# badge.net
KiCad netlist of a schematic drawn in EAGLE
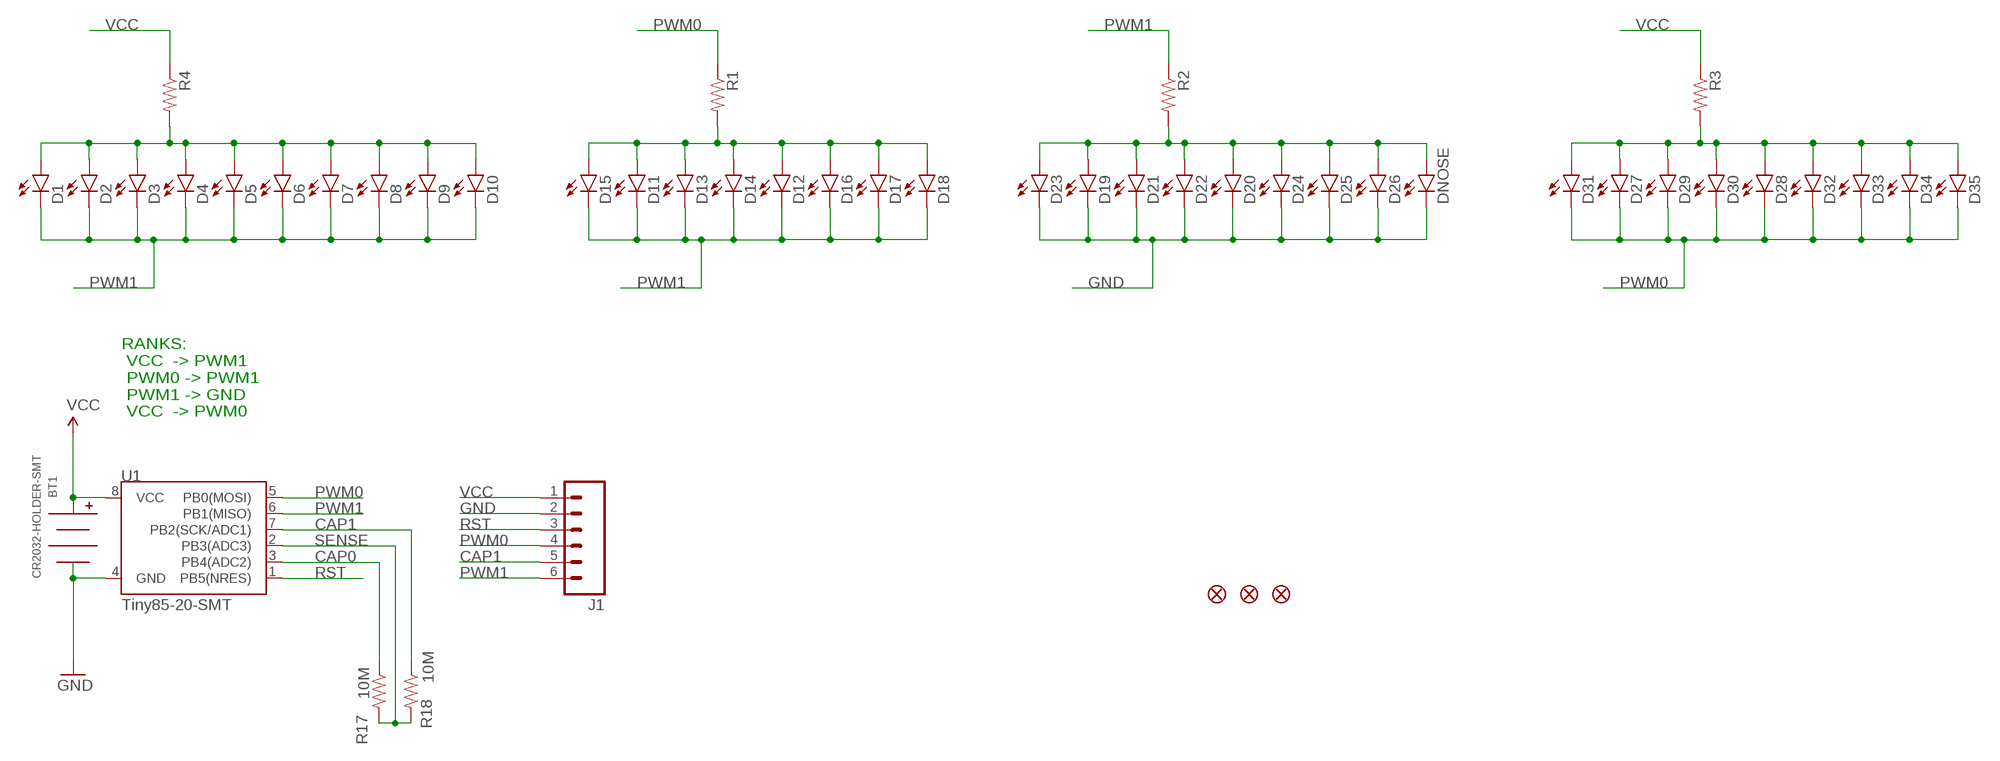
[diagram p0: schematic, sheet 1]

(export (version "E")
  (design (tool "Eeschema 10.0.6"))
  (components
    (comp (ref "BT1")
      (value "CR2032-HOLDER-SMT")
      (footprint "eagle-import:S8211-46R")
      (libsource (lib "eagle-import") (part "CR2032-HOLDER-SMT"))
    )
    (comp (ref "D1")
      (value "LED0603")
      (footprint "eagle-import:LED-0603")
      (libsource (lib "eagle-import") (part "LED0603"))
    )
    (comp (ref "D2")
      (value "LED0603")
      (footprint "eagle-import:LED-0603")
      (libsource (lib "eagle-import") (part "LED0603"))
    )
    (comp (ref "D3")
      (value "LED0603")
      (footprint "eagle-import:LED-0603")
      (libsource (lib "eagle-import") (part "LED0603"))
    )
    (comp (ref "D4")
      (value "LED0603")
      (footprint "eagle-import:LED-0603")
      (libsource (lib "eagle-import") (part "LED0603"))
    )
    (comp (ref "D5")
      (value "LED0603")
      (footprint "eagle-import:LED-0603")
      (libsource (lib "eagle-import") (part "LED0603"))
    )
    (comp (ref "D6")
      (value "LED0603")
      (footprint "eagle-import:LED-0603")
      (libsource (lib "eagle-import") (part "LED0603"))
    )
    (comp (ref "D7")
      (value "LED0603")
      (footprint "eagle-import:LED-0603")
      (libsource (lib "eagle-import") (part "LED0603"))
    )
    (comp (ref "D8")
      (value "LED0603")
      (footprint "eagle-import:LED-0603")
      (libsource (lib "eagle-import") (part "LED0603"))
    )
    (comp (ref "D9")
      (value "LED0603")
      (footprint "eagle-import:LED-0603")
      (libsource (lib "eagle-import") (part "LED0603"))
    )
    (comp (ref "D10")
      (value "LED0603")
      (footprint "eagle-import:LED-0603")
      (libsource (lib "eagle-import") (part "LED0603"))
    )
    (comp (ref "D11")
      (value "LED0603")
      (footprint "eagle-import:LED-0603")
      (libsource (lib "eagle-import") (part "LED0603"))
    )
    (comp (ref "D12")
      (value "LED0603")
      (footprint "eagle-import:LED-0603")
      (libsource (lib "eagle-import") (part "LED0603"))
    )
    (comp (ref "D13")
      (value "LED0603")
      (footprint "eagle-import:LED-0603")
      (libsource (lib "eagle-import") (part "LED0603"))
    )
    (comp (ref "D14")
      (value "LED0603")
      (footprint "eagle-import:LED-0603")
      (libsource (lib "eagle-import") (part "LED0603"))
    )
    (comp (ref "D15")
      (value "LED0603")
      (footprint "eagle-import:LED-0603")
      (libsource (lib "eagle-import") (part "LED0603"))
    )
    (comp (ref "D16")
      (value "LED0603")
      (footprint "eagle-import:LED-0603")
      (libsource (lib "eagle-import") (part "LED0603"))
    )
    (comp (ref "D17")
      (value "LED0603")
      (footprint "eagle-import:LED-0603")
      (libsource (lib "eagle-import") (part "LED0603"))
    )
    (comp (ref "D18")
      (value "LED0603")
      (footprint "eagle-import:LED-0603")
      (libsource (lib "eagle-import") (part "LED0603"))
    )
    (comp (ref "D19")
      (value "LED0603")
      (footprint "eagle-import:LED-0603")
      (libsource (lib "eagle-import") (part "LED0603"))
    )
    (comp (ref "D20")
      (value "LED0603")
      (footprint "eagle-import:LED-0603")
      (libsource (lib "eagle-import") (part "LED0603"))
    )
    (comp (ref "D21")
      (value "LED0603")
      (footprint "eagle-import:LED-0603")
      (libsource (lib "eagle-import") (part "LED0603"))
    )
    (comp (ref "D22")
      (value "LED0603")
      (footprint "eagle-import:LED-0603")
      (libsource (lib "eagle-import") (part "LED0603"))
    )
    (comp (ref "D23")
      (value "LED0603")
      (footprint "eagle-import:LED-0603")
      (libsource (lib "eagle-import") (part "LED0603"))
    )
    (comp (ref "D24")
      (value "LED0603")
      (footprint "eagle-import:LED-0603")
      (libsource (lib "eagle-import") (part "LED0603"))
    )
    (comp (ref "D25")
      (value "LED0603")
      (footprint "eagle-import:LED-0603")
      (libsource (lib "eagle-import") (part "LED0603"))
    )
    (comp (ref "D26")
      (value "LED0603")
      (footprint "eagle-import:LED-0603")
      (libsource (lib "eagle-import") (part "LED0603"))
    )
    (comp (ref "D27")
      (value "LED0603")
      (footprint "eagle-import:LED-0603")
      (libsource (lib "eagle-import") (part "LED0603"))
    )
    (comp (ref "D28")
      (value "LED0603")
      (footprint "eagle-import:LED-0603")
      (libsource (lib "eagle-import") (part "LED0603"))
    )
    (comp (ref "D29")
      (value "LED0603")
      (footprint "eagle-import:LED-0603")
      (libsource (lib "eagle-import") (part "LED0603"))
    )
    (comp (ref "D30")
      (value "LED0603")
      (footprint "eagle-import:LED-0603")
      (libsource (lib "eagle-import") (part "LED0603"))
    )
    (comp (ref "D31")
      (value "LED0603")
      (footprint "eagle-import:LED-0603")
      (libsource (lib "eagle-import") (part "LED0603"))
    )
    (comp (ref "D32")
      (value "LED0603")
      (footprint "eagle-import:LED-0603")
      (libsource (lib "eagle-import") (part "LED0603"))
    )
    (comp (ref "D33")
      (value "LED0603")
      (footprint "eagle-import:LED-0603")
      (libsource (lib "eagle-import") (part "LED0603"))
    )
    (comp (ref "D34")
      (value "LED0603")
      (footprint "eagle-import:LED-0603")
      (libsource (lib "eagle-import") (part "LED0603"))
    )
    (comp (ref "D35")
      (value "LED0603")
      (footprint "eagle-import:LED-0603")
      (libsource (lib "eagle-import") (part "LED0603"))
    )
    (comp (ref "DNOSE")
      (value "LED0603")
      (footprint "eagle-import:LED-0603")
      (libsource (lib "eagle-import") (part "LED0603"))
    )
    (comp (ref "FD1")
      (value "FIDUCIAL1X2")
      (footprint "eagle-import:FIDUCIAL-1X2")
      (libsource (lib "eagle-import") (part "FIDUCIAL1X2"))
    )
    (comp (ref "FD2")
      (value "FIDUCIAL1X2")
      (footprint "eagle-import:FIDUCIAL-1X2")
      (libsource (lib "eagle-import") (part "FIDUCIAL1X2"))
    )
    (comp (ref "FD3")
      (value "FIDUCIAL1X2")
      (footprint "eagle-import:FIDUCIAL-1X2")
      (libsource (lib "eagle-import") (part "FIDUCIAL1X2"))
    )
    (comp (ref "J1")
      (value "M06LONGPADS")
      (footprint "eagle-import:1X06_LONGPADS")
      (libsource (lib "eagle-import") (part "M06LONGPADS"))
    )
    (comp (ref "R1")
      (value "RESISTOR1206")
      (footprint "eagle-import:1206")
      (libsource (lib "eagle-import") (part "RESISTOR1206"))
    )
    (comp (ref "R2")
      (value "RESISTOR1206")
      (footprint "eagle-import:1206")
      (libsource (lib "eagle-import") (part "RESISTOR1206"))
    )
    (comp (ref "R3")
      (value "RESISTOR1206")
      (footprint "eagle-import:1206")
      (libsource (lib "eagle-import") (part "RESISTOR1206"))
    )
    (comp (ref "R4")
      (value "RESISTOR1206")
      (footprint "eagle-import:1206")
      (libsource (lib "eagle-import") (part "RESISTOR1206"))
    )
    (comp (ref "R17")
      (value "10M")
      (footprint "eagle-import:0805")
      (libsource (lib "eagle-import") (part "RESISTOR0805-RES"))
    )
    (comp (ref "R18")
      (value "10M")
      (footprint "eagle-import:0805")
      (libsource (lib "eagle-import") (part "RESISTOR0805-RES"))
    )
    (comp (ref "U1")
      (value "Tiny85-20-SMT")
      (footprint "eagle-import:SO08-EIAJ")
      (libsource (lib "eagle-import") (part "ATTINY45TINY85-20-SMT"))
    )
  )
  (nets
    (net (code "1") (name "/CAP0") (class "Default")
      (node (ref "R17") (pin "1") (pinfunction "1_1") (pintype "passive"))
      (node (ref "U1") (pin "3") (pinfunction "PB4(ADC2)_3") (pintype "bidirectional"))
    )
    (net (code "2") (name "/CAP1") (class "Default")
      (node (ref "J1") (pin "5") (pinfunction "5_5") (pintype "passive"))
      (node (ref "R18") (pin "1") (pinfunction "1_1") (pintype "passive"))
      (node (ref "U1") (pin "7") (pinfunction "PB2(SCK/ADC1)_7") (pintype "bidirectional"))
    )
    (net (code "3") (name "/PWM0") (class "Default")
      (node (ref "D27") (pin "C") (pinfunction "C_C") (pintype "passive"))
      (node (ref "D28") (pin "C") (pinfunction "C_C") (pintype "passive"))
      (node (ref "D29") (pin "C") (pinfunction "C_C") (pintype "passive"))
      (node (ref "D30") (pin "C") (pinfunction "C_C") (pintype "passive"))
      (node (ref "D31") (pin "C") (pinfunction "C_C") (pintype "passive"))
      (node (ref "D32") (pin "C") (pinfunction "C_C") (pintype "passive"))
      (node (ref "D33") (pin "C") (pinfunction "C_C") (pintype "passive"))
      (node (ref "D34") (pin "C") (pinfunction "C_C") (pintype "passive"))
      (node (ref "D35") (pin "C") (pinfunction "C_C") (pintype "passive"))
      (node (ref "J1") (pin "4") (pinfunction "4_4") (pintype "passive"))
      (node (ref "R1") (pin "1") (pinfunction "1_1") (pintype "passive"))
      (node (ref "U1") (pin "5") (pinfunction "PB0(MOSI)_5") (pintype "bidirectional"))
    )
    (net (code "4") (name "/PWM1") (class "Default")
      (node (ref "D1") (pin "C") (pinfunction "C_C") (pintype "passive"))
      (node (ref "D10") (pin "C") (pinfunction "C_C") (pintype "passive"))
      (node (ref "D11") (pin "C") (pinfunction "C_C") (pintype "passive"))
      (node (ref "D12") (pin "C") (pinfunction "C_C") (pintype "passive"))
      (node (ref "D13") (pin "C") (pinfunction "C_C") (pintype "passive"))
      (node (ref "D14") (pin "C") (pinfunction "C_C") (pintype "passive"))
      (node (ref "D15") (pin "C") (pinfunction "C_C") (pintype "passive"))
      (node (ref "D16") (pin "C") (pinfunction "C_C") (pintype "passive"))
      (node (ref "D17") (pin "C") (pinfunction "C_C") (pintype "passive"))
      (node (ref "D18") (pin "C") (pinfunction "C_C") (pintype "passive"))
      (node (ref "D2") (pin "C") (pinfunction "C_C") (pintype "passive"))
      (node (ref "D3") (pin "C") (pinfunction "C_C") (pintype "passive"))
      (node (ref "D4") (pin "C") (pinfunction "C_C") (pintype "passive"))
      (node (ref "D5") (pin "C") (pinfunction "C_C") (pintype "passive"))
      (node (ref "D6") (pin "C") (pinfunction "C_C") (pintype "passive"))
      (node (ref "D7") (pin "C") (pinfunction "C_C") (pintype "passive"))
      (node (ref "D8") (pin "C") (pinfunction "C_C") (pintype "passive"))
      (node (ref "D9") (pin "C") (pinfunction "C_C") (pintype "passive"))
      (node (ref "J1") (pin "6") (pinfunction "6_6") (pintype "passive"))
      (node (ref "R2") (pin "1") (pinfunction "1_1") (pintype "passive"))
      (node (ref "U1") (pin "6") (pinfunction "PB1(MISO)_6") (pintype "bidirectional"))
    )
    (net (code "5") (name "/RST") (class "Default")
      (node (ref "J1") (pin "3") (pinfunction "3_3") (pintype "passive"))
      (node (ref "U1") (pin "1") (pinfunction "PB5(NRES)_1") (pintype "bidirectional"))
    )
    (net (code "6") (name "/SENSE") (class "Default")
      (node (ref "R17") (pin "2") (pinfunction "2_2") (pintype "passive"))
      (node (ref "R18") (pin "2") (pinfunction "2_2") (pintype "passive"))
      (node (ref "U1") (pin "2") (pinfunction "PB3(ADC3)_2") (pintype "bidirectional"))
    )
    (net (code "7") (name "GND") (class "Default")
      (node (ref "BT1") (pin "NEG") (pinfunction "NEG_NEG") (pintype "bidirectional"))
      (node (ref "D19") (pin "C") (pinfunction "C_C") (pintype "passive"))
      (node (ref "D20") (pin "C") (pinfunction "C_C") (pintype "passive"))
      (node (ref "D21") (pin "C") (pinfunction "C_C") (pintype "passive"))
      (node (ref "D22") (pin "C") (pinfunction "C_C") (pintype "passive"))
      (node (ref "D23") (pin "C") (pinfunction "C_C") (pintype "passive"))
      (node (ref "D24") (pin "C") (pinfunction "C_C") (pintype "passive"))
      (node (ref "D25") (pin "C") (pinfunction "C_C") (pintype "passive"))
      (node (ref "D26") (pin "C") (pinfunction "C_C") (pintype "passive"))
      (node (ref "DNOSE") (pin "C") (pinfunction "C_C") (pintype "passive"))
      (node (ref "J1") (pin "2") (pinfunction "2_2") (pintype "passive"))
      (node (ref "U1") (pin "4") (pinfunction "GND_4") (pintype "bidirectional"))
    )
    (net (code "8") (name "Net-(D1-PadA)") (class "Default")
      (node (ref "D1") (pin "A") (pinfunction "A_A") (pintype "passive"))
      (node (ref "D10") (pin "A") (pinfunction "A_A") (pintype "passive"))
      (node (ref "D2") (pin "A") (pinfunction "A_A") (pintype "passive"))
      (node (ref "D3") (pin "A") (pinfunction "A_A") (pintype "passive"))
      (node (ref "D4") (pin "A") (pinfunction "A_A") (pintype "passive"))
      (node (ref "D5") (pin "A") (pinfunction "A_A") (pintype "passive"))
      (node (ref "D6") (pin "A") (pinfunction "A_A") (pintype "passive"))
      (node (ref "D7") (pin "A") (pinfunction "A_A") (pintype "passive"))
      (node (ref "D8") (pin "A") (pinfunction "A_A") (pintype "passive"))
      (node (ref "D9") (pin "A") (pinfunction "A_A") (pintype "passive"))
      (node (ref "R4") (pin "2") (pinfunction "2_2") (pintype "passive"))
    )
    (net (code "9") (name "Net-(D11-PadA)") (class "Default")
      (node (ref "D11") (pin "A") (pinfunction "A_A") (pintype "passive"))
      (node (ref "D12") (pin "A") (pinfunction "A_A") (pintype "passive"))
      (node (ref "D13") (pin "A") (pinfunction "A_A") (pintype "passive"))
      (node (ref "D14") (pin "A") (pinfunction "A_A") (pintype "passive"))
      (node (ref "D15") (pin "A") (pinfunction "A_A") (pintype "passive"))
      (node (ref "D16") (pin "A") (pinfunction "A_A") (pintype "passive"))
      (node (ref "D17") (pin "A") (pinfunction "A_A") (pintype "passive"))
      (node (ref "D18") (pin "A") (pinfunction "A_A") (pintype "passive"))
      (node (ref "R1") (pin "2") (pinfunction "2_2") (pintype "passive"))
    )
    (net (code "10") (name "Net-(D19-PadA)") (class "Default")
      (node (ref "D19") (pin "A") (pinfunction "A_A") (pintype "passive"))
      (node (ref "D20") (pin "A") (pinfunction "A_A") (pintype "passive"))
      (node (ref "D21") (pin "A") (pinfunction "A_A") (pintype "passive"))
      (node (ref "D22") (pin "A") (pinfunction "A_A") (pintype "passive"))
      (node (ref "D23") (pin "A") (pinfunction "A_A") (pintype "passive"))
      (node (ref "D24") (pin "A") (pinfunction "A_A") (pintype "passive"))
      (node (ref "D25") (pin "A") (pinfunction "A_A") (pintype "passive"))
      (node (ref "D26") (pin "A") (pinfunction "A_A") (pintype "passive"))
      (node (ref "DNOSE") (pin "A") (pinfunction "A_A") (pintype "passive"))
      (node (ref "R2") (pin "2") (pinfunction "2_2") (pintype "passive"))
    )
    (net (code "11") (name "Net-(D27-PadA)") (class "Default")
      (node (ref "D27") (pin "A") (pinfunction "A_A") (pintype "passive"))
      (node (ref "D28") (pin "A") (pinfunction "A_A") (pintype "passive"))
      (node (ref "D29") (pin "A") (pinfunction "A_A") (pintype "passive"))
      (node (ref "D30") (pin "A") (pinfunction "A_A") (pintype "passive"))
      (node (ref "D31") (pin "A") (pinfunction "A_A") (pintype "passive"))
      (node (ref "D32") (pin "A") (pinfunction "A_A") (pintype "passive"))
      (node (ref "D33") (pin "A") (pinfunction "A_A") (pintype "passive"))
      (node (ref "D34") (pin "A") (pinfunction "A_A") (pintype "passive"))
      (node (ref "D35") (pin "A") (pinfunction "A_A") (pintype "passive"))
      (node (ref "R3") (pin "2") (pinfunction "2_2") (pintype "passive"))
    )
    (net (code "12") (name "VCC") (class "Default")
      (node (ref "BT1") (pin "POS0") (pinfunction "POS_POS0") (pintype "bidirectional"))
      (node (ref "BT1") (pin "POS1") (pinfunction "POS_POS1") (pintype "bidirectional"))
      (node (ref "J1") (pin "1") (pinfunction "1_1") (pintype "passive"))
      (node (ref "R3") (pin "1") (pinfunction "1_1") (pintype "passive"))
      (node (ref "R4") (pin "1") (pinfunction "1_1") (pintype "passive"))
      (node (ref "U1") (pin "8") (pinfunction "VCC_8") (pintype "bidirectional"))
    )
  )
)
